# power.net
KiCad netlist of a schematic drawn in EAGLE
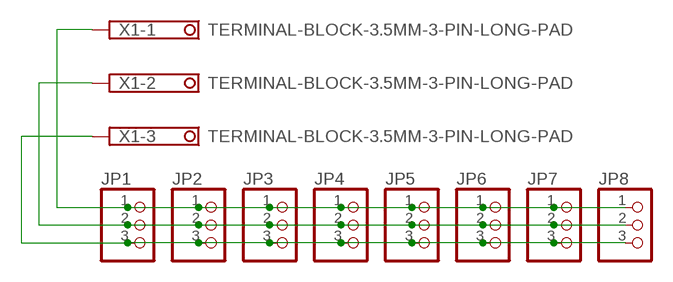
[diagram p0: schematic, sheet 1]

(export (version "E")
  (design (tool "Eeschema 10.0.6"))
  (components
    (comp (ref "JP1")
      (value "PINHD-1X3/90")
      (footprint "eagle-import:1X03_90")
      (libsource (lib "eagle-import") (part "PINHD-1X3/90"))
    )
    (comp (ref "JP2")
      (value "PINHD-1X3/90")
      (footprint "eagle-import:1X03_90")
      (libsource (lib "eagle-import") (part "PINHD-1X3/90"))
    )
    (comp (ref "JP3")
      (value "PINHD-1X3/90")
      (footprint "eagle-import:1X03_90")
      (libsource (lib "eagle-import") (part "PINHD-1X3/90"))
    )
    (comp (ref "JP4")
      (value "PINHD-1X3/90")
      (footprint "eagle-import:1X03_90")
      (libsource (lib "eagle-import") (part "PINHD-1X3/90"))
    )
    (comp (ref "JP5")
      (value "PINHD-1X3/90")
      (footprint "eagle-import:1X03_90")
      (libsource (lib "eagle-import") (part "PINHD-1X3/90"))
    )
    (comp (ref "JP6")
      (value "PINHD-1X3/90")
      (footprint "eagle-import:1X03_90")
      (libsource (lib "eagle-import") (part "PINHD-1X3/90"))
    )
    (comp (ref "JP7")
      (value "PINHD-1X3/90")
      (footprint "eagle-import:1X03_90")
      (libsource (lib "eagle-import") (part "PINHD-1X3/90"))
    )
    (comp (ref "JP8")
      (value "PINHD-1X3/90")
      (footprint "eagle-import:1X03_90")
      (libsource (lib "eagle-import") (part "PINHD-1X3/90"))
    )
    (comp (ref "X1")
      (value "TERMINAL-BLOCK-3.5MM-3-PIN-LONG-PAD")
      (footprint "eagle-import:TERMINAL-BLOCK-3-PIN-3.5MM-LONG-PAD")
      (libsource (lib "eagle-import") (part "TERMINAL-BLOCK-3.5MM-3-PIN-LONG-PAD"))
    )
  )
  (nets
    (net (code "1") (name "Net-(X1A-K)") (class "Default")
      (node (ref "JP1") (pin "1") (pinfunction "1_1") (pintype "passive"))
      (node (ref "JP2") (pin "1") (pinfunction "1_1") (pintype "passive"))
      (node (ref "JP3") (pin "1") (pinfunction "1_1") (pintype "passive"))
      (node (ref "JP4") (pin "1") (pinfunction "1_1") (pintype "passive"))
      (node (ref "JP5") (pin "1") (pinfunction "1_1") (pintype "passive"))
      (node (ref "JP6") (pin "1") (pinfunction "1_1") (pintype "passive"))
      (node (ref "JP7") (pin "1") (pinfunction "1_1") (pintype "passive"))
      (node (ref "JP8") (pin "1") (pinfunction "1_1") (pintype "passive"))
      (node (ref "X1") (pin "1") (pinfunction "K_1") (pintype "passive"))
    )
    (net (code "2") (name "Net-(X1B-K)") (class "Default")
      (node (ref "JP1") (pin "2") (pinfunction "2_2") (pintype "passive"))
      (node (ref "JP2") (pin "2") (pinfunction "2_2") (pintype "passive"))
      (node (ref "JP3") (pin "2") (pinfunction "2_2") (pintype "passive"))
      (node (ref "JP4") (pin "2") (pinfunction "2_2") (pintype "passive"))
      (node (ref "JP5") (pin "2") (pinfunction "2_2") (pintype "passive"))
      (node (ref "JP6") (pin "2") (pinfunction "2_2") (pintype "passive"))
      (node (ref "JP7") (pin "2") (pinfunction "2_2") (pintype "passive"))
      (node (ref "JP8") (pin "2") (pinfunction "2_2") (pintype "passive"))
      (node (ref "X1") (pin "2") (pinfunction "K_2") (pintype "passive"))
    )
    (net (code "3") (name "Net-(X1C-K)") (class "Default")
      (node (ref "JP1") (pin "3") (pinfunction "3_3") (pintype "passive"))
      (node (ref "JP2") (pin "3") (pinfunction "3_3") (pintype "passive"))
      (node (ref "JP3") (pin "3") (pinfunction "3_3") (pintype "passive"))
      (node (ref "JP4") (pin "3") (pinfunction "3_3") (pintype "passive"))
      (node (ref "JP5") (pin "3") (pinfunction "3_3") (pintype "passive"))
      (node (ref "JP6") (pin "3") (pinfunction "3_3") (pintype "passive"))
      (node (ref "JP7") (pin "3") (pinfunction "3_3") (pintype "passive"))
      (node (ref "JP8") (pin "3") (pinfunction "3_3") (pintype "passive"))
      (node (ref "X1") (pin "3") (pinfunction "K_3") (pintype "passive"))
    )
  )
)
